# usb-breakout.net
KiCad netlist of a schematic drawn in EAGLE
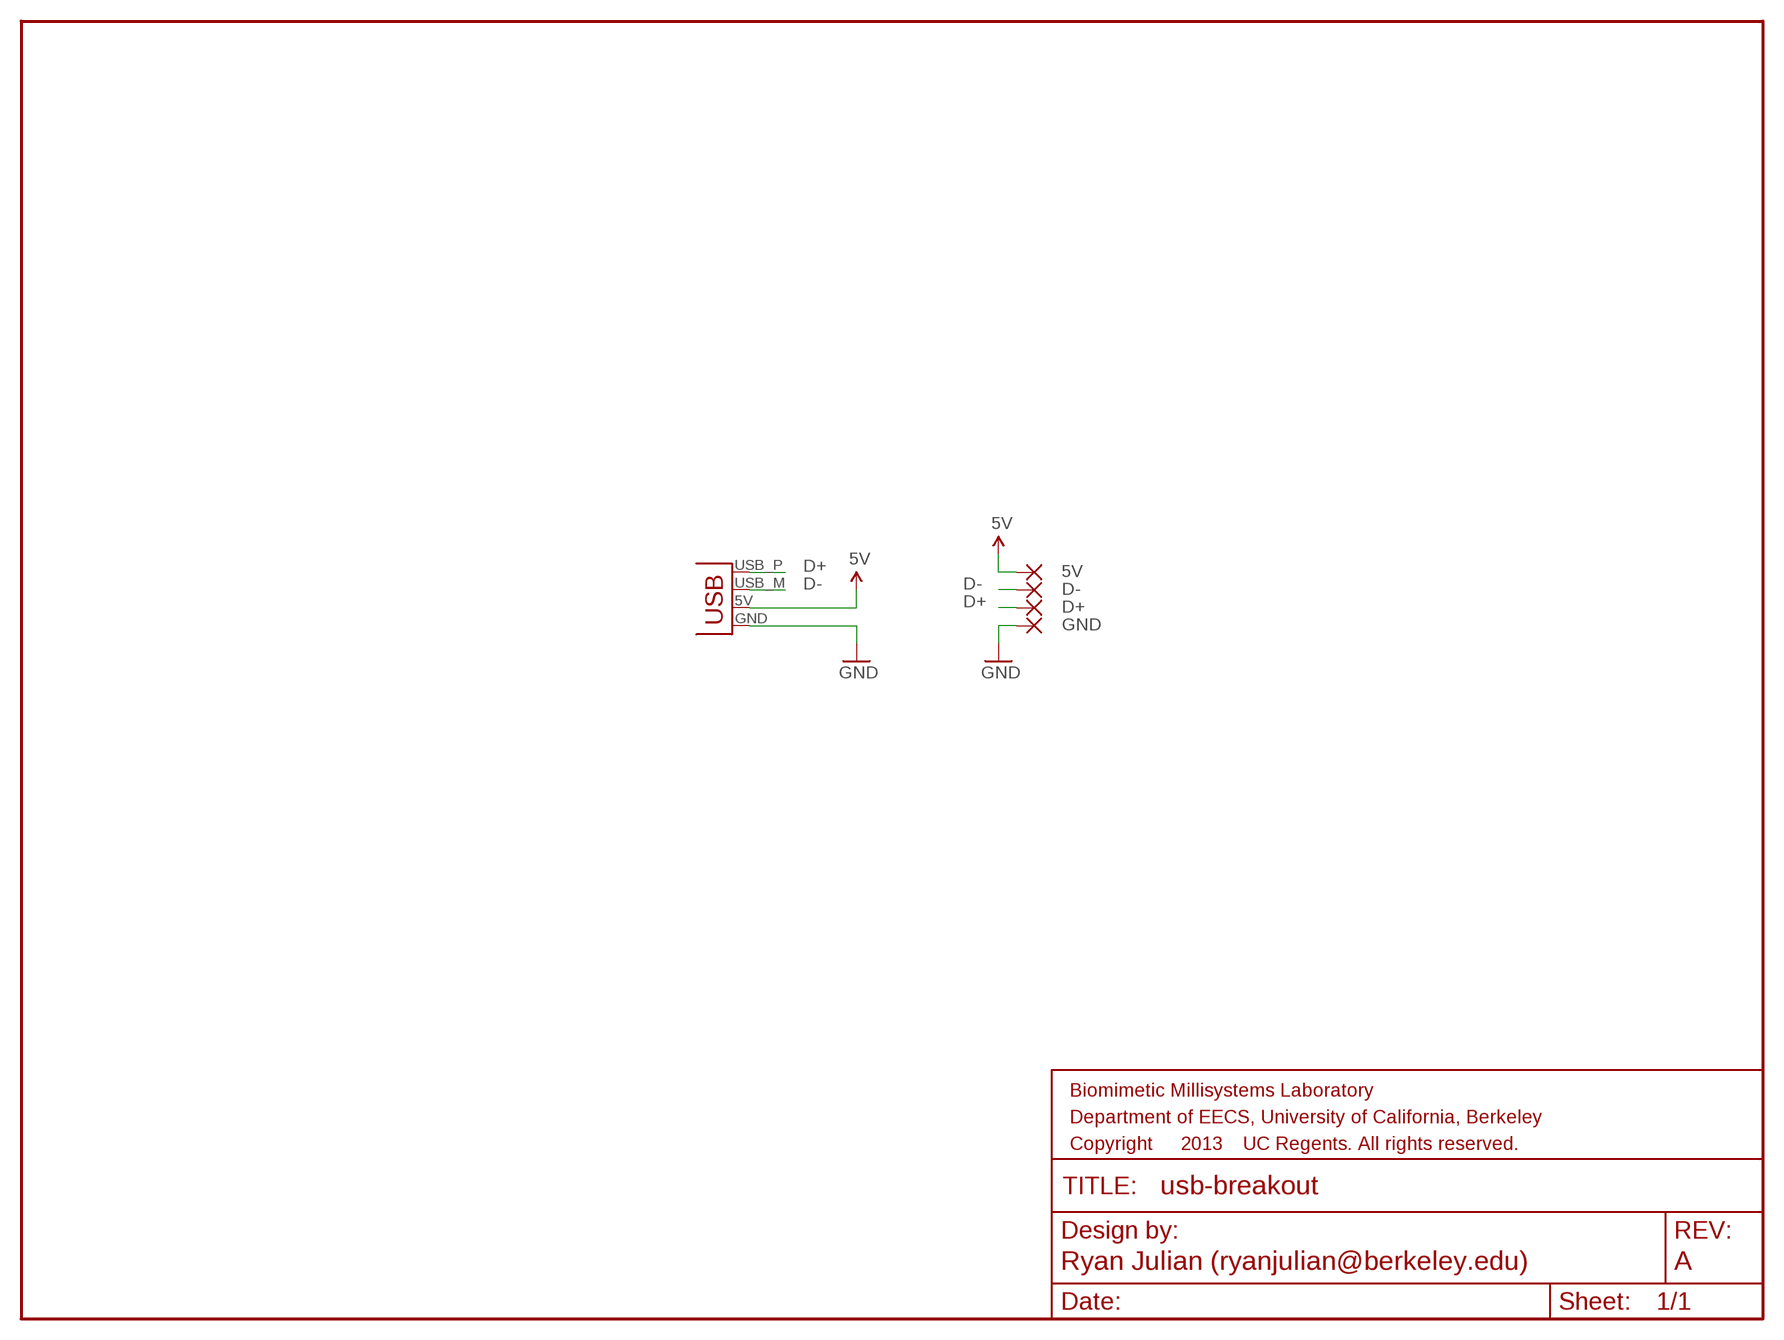
[diagram p0: schematic, sheet 1]

(export (version "E")
  (design (tool "Eeschema 10.0.6"))
  (components
    (comp (ref "JP1")
      (value "USBPCB")
      (footprint "eagle-import:USB-A-PCB")
      (libsource (lib "eagle-import") (part "USBPCB"))
    )
    (comp (ref "PAD1")
      (value "GND")
      (footprint "eagle-import:5-1,8")
      (libsource (lib "eagle-import") (part "WIREPADSMD5-1,8"))
    )
    (comp (ref "PAD2")
      (value "D+")
      (footprint "eagle-import:5-1,8")
      (libsource (lib "eagle-import") (part "WIREPADSMD5-1,8"))
    )
    (comp (ref "PAD3")
      (value "D-")
      (footprint "eagle-import:5-1,8")
      (libsource (lib "eagle-import") (part "WIREPADSMD5-1,8"))
    )
    (comp (ref "PAD4")
      (value "5V")
      (footprint "eagle-import:5-1,8")
      (libsource (lib "eagle-import") (part "WIREPADSMD5-1,8"))
    )
  )
  (nets
    (net (code "1") (name "/D+") (class "Default")
      (node (ref "JP1") (pin "USB_P") (pinfunction "D+_USB_P") (pintype "bidirectional"))
      (node (ref "PAD2") (pin "1") (pinfunction "P_1") (pintype "passive"))
    )
    (net (code "2") (name "/D-") (class "Default")
      (node (ref "JP1") (pin "USB_M") (pinfunction "D-_USB_M") (pintype "bidirectional"))
      (node (ref "PAD3") (pin "1") (pinfunction "P_1") (pintype "passive"))
    )
    (net (code "3") (name "5V") (class "Default")
      (node (ref "JP1") (pin "5V") (pinfunction "VBUS_5V") (pintype "bidirectional"))
      (node (ref "PAD4") (pin "1") (pinfunction "P_1") (pintype "passive"))
    )
    (net (code "4") (name "GND") (class "Default")
      (node (ref "JP1") (pin "GND") (pinfunction "GND_GND") (pintype "bidirectional"))
      (node (ref "PAD1") (pin "1") (pinfunction "P_1") (pintype "passive"))
    )
  )
)
